# Half_Slave.net
KiCad netlist of a schematic drawn in Altium Designer
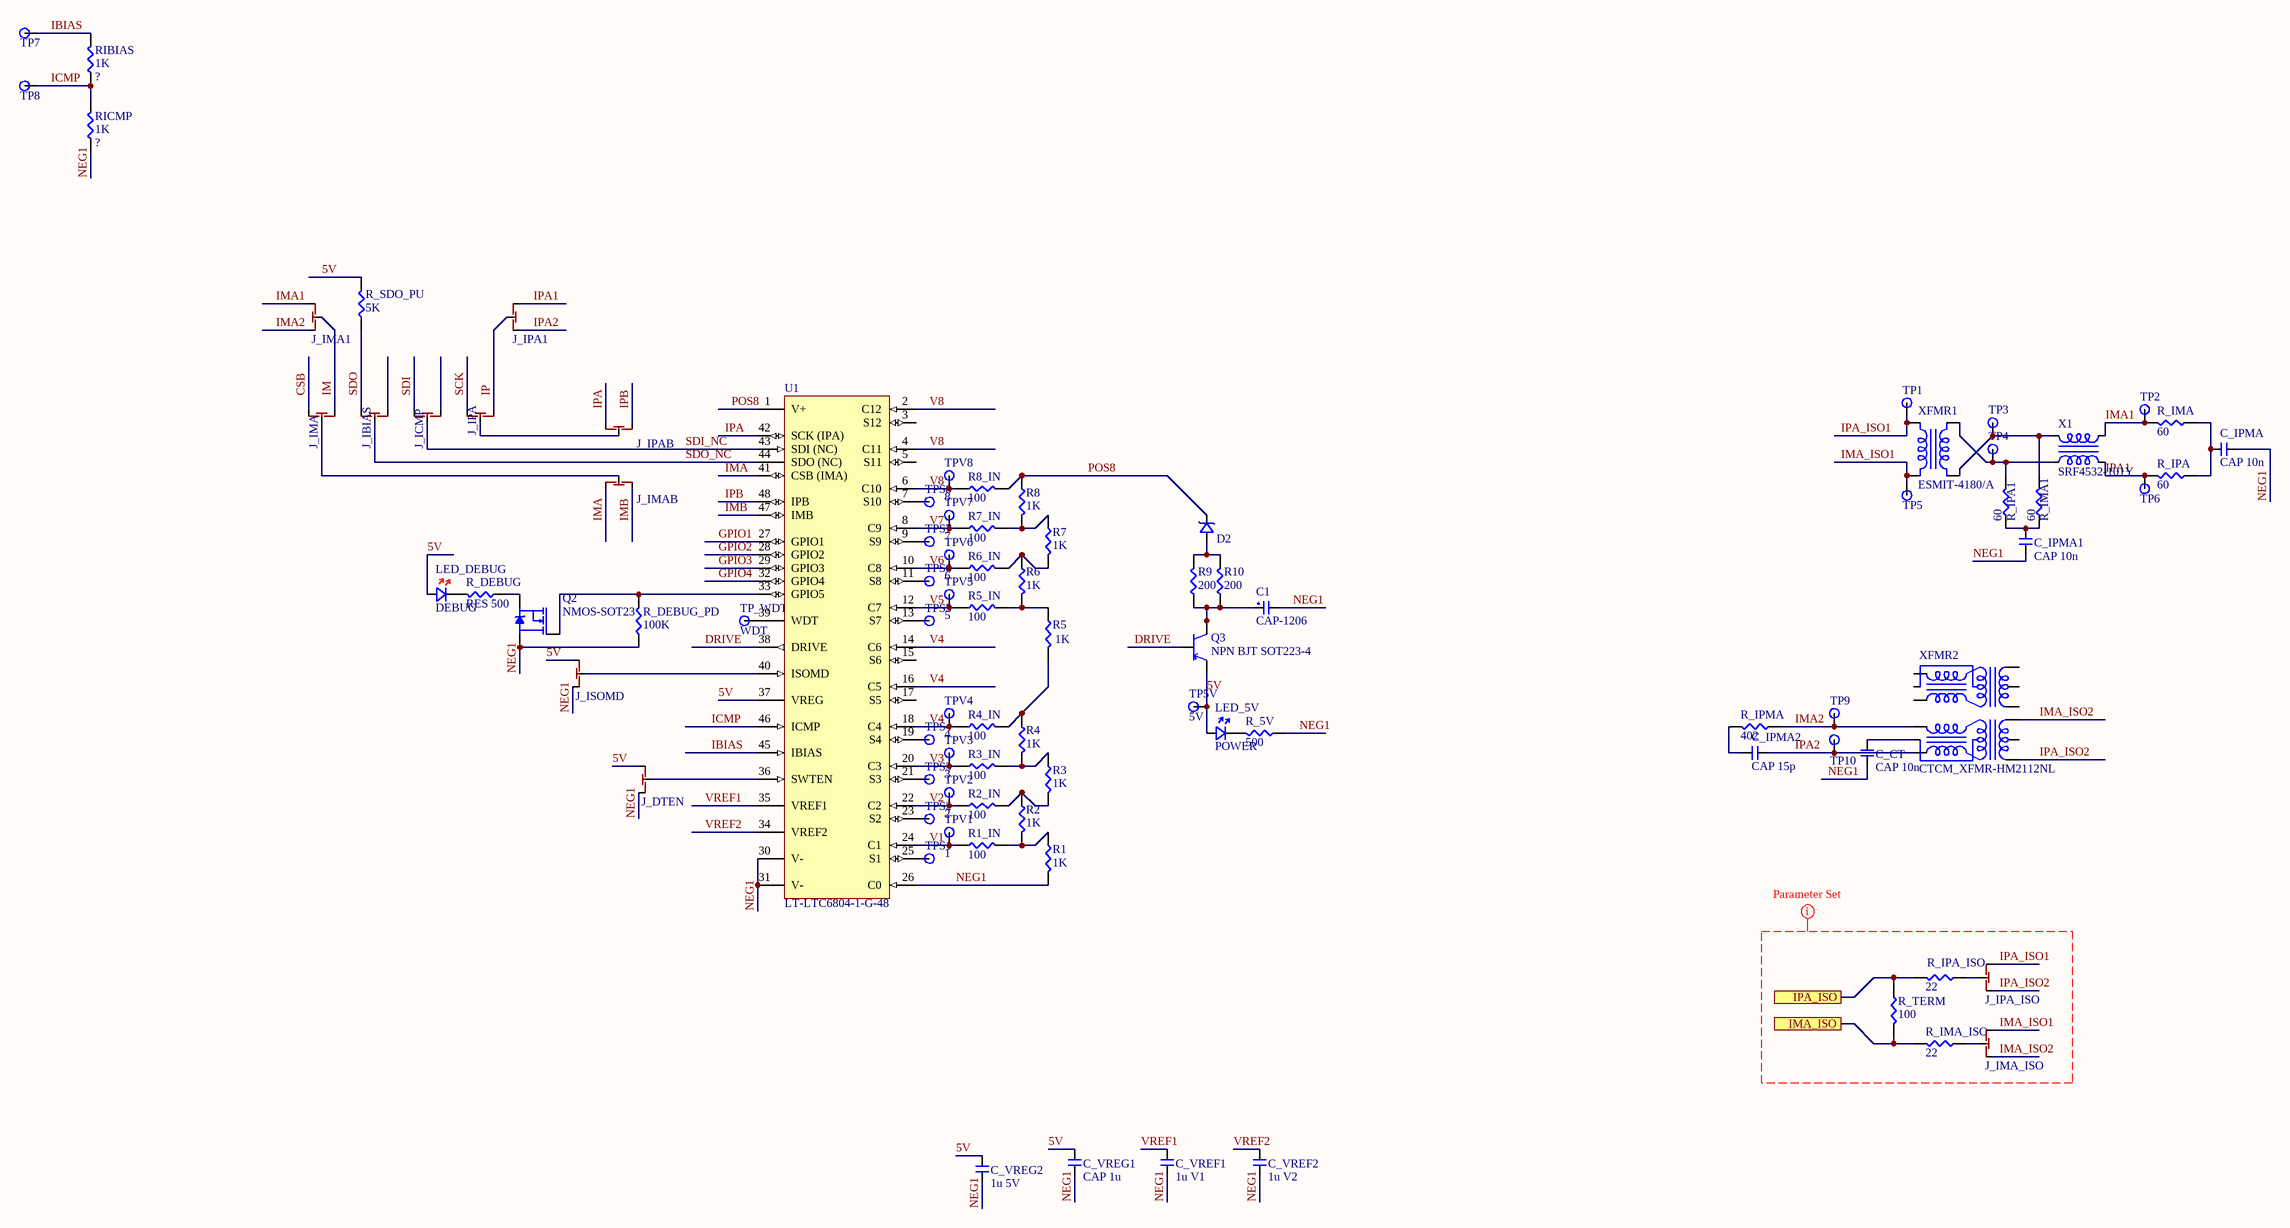
[diagram p0: Half_Slave.SchDoc]

(export (version "E")
  (design (tool "Eeschema 10.0.6"))
  (components
    (comp (ref "C1")
      (value "CAP-1206")
      (footprint "CAPCP3216X16N")
      (libsource (lib "LTC6811") (part "CAP-1206"))
    )
    (comp (ref "C_CT")
      (value "CAP 10n")
      (footprint "CAP-0603")
      (description "CAP-0603")
      (libsource (lib "ife18_TS_BMS_LTC6813_v2_Library") (part "CAP-0603"))
    )
    (comp (ref "C_IPMA")
      (value "CAP 10n")
      (footprint "CAP-0603")
      (description "CAP-0603")
      (libsource (lib "ife18_TS_BMS_LTC6813_v2_Library") (part "CAP-0603"))
    )
    (comp (ref "C_IPMA1")
      (value "CAP 10n")
      (footprint "CAP-0603")
      (description "CAP-0603")
      (libsource (lib "ife18_TS_BMS_LTC6813_v2_Library") (part "CAP-0603"))
    )
    (comp (ref "C_IPMA2")
      (value "CAP 15p")
      (footprint "CAP-0603")
      (description "CAP-0603")
      (libsource (lib "ife18_TS_BMS_LTC6813_v2_Library") (part "CAP-0603"))
    )
    (comp (ref "C_VREF1")
      (value "1u V1")
      (footprint "CAP-0603")
      (description "CAP-0603")
      (libsource (lib "altium-import") (part "root_1_CAP-0603_"))
    )
    (comp (ref "C_VREF2")
      (value "1u V2")
      (footprint "CAP-0603")
      (description "CAP-0603")
      (libsource (lib "altium-import") (part "root_1_CAP-0603_"))
    )
    (comp (ref "C_VREG1")
      (value "CAP 1u")
      (footprint "CAP-0603")
      (description "CAP-0603")
      (libsource (lib "altium-import") (part "root_1_CAP-0603_"))
    )
    (comp (ref "C_VREG2")
      (value "1u 5V")
      (footprint "CAP-0603")
      (description "CAP-0603")
      (libsource (lib "altium-import") (part "root_1_CAP-0603_"))
    )
    (comp (ref "D2") (value "?") (footprint "SMB") (libsource (lib "ife19_Elec_Library") (part "DIODE-SMB")))
    (comp (ref "J_DTEN")
      (value "DPDT Solder Jumper")
      (footprint "DPDT Solder")
      (libsource (lib "LTC6811") (part "DPDT Solder"))
    )
    (comp (ref "J_IBIAS")
      (value "DPDT Solder Jumper")
      (footprint "DPDT Solder")
      (libsource (lib "LTC6811") (part "DPDT Solder"))
    )
    (comp (ref "J_ICMP")
      (value "DPDT Solder Jumper")
      (footprint "DPDT Solder")
      (libsource (lib "LTC6811") (part "DPDT Solder"))
    )
    (comp (ref "J_IMA")
      (value "DPDT Solder Jumper")
      (footprint "DPDT Solder")
      (libsource (lib "LTC6811") (part "DPDT Solder"))
    )
    (comp (ref "J_IMA1")
      (value "DPDT Solder Jumper")
      (footprint "DPDT Solder")
      (libsource (lib "LTC6811") (part "DPDT Solder"))
    )
    (comp (ref "J_IMAB")
      (value "DPDT Solder Jumper")
      (footprint "DPDT Solder")
      (libsource (lib "LTC6811") (part "DPDT Solder"))
    )
    (comp (ref "J_IMA_ISO")
      (value "DPDT Solder Jumper")
      (footprint "DPDT Solder")
      (libsource (lib "LTC6811") (part "DPDT Solder"))
    )
    (comp (ref "J_IPA")
      (value "DPDT Solder Jumper")
      (footprint "DPDT Solder")
      (libsource (lib "LTC6811") (part "DPDT Solder"))
    )
    (comp (ref "J_IPA1")
      (value "DPDT Solder Jumper")
      (footprint "DPDT Solder")
      (libsource (lib "LTC6811") (part "DPDT Solder"))
    )
    (comp (ref "J_IPAB")
      (value "DPDT Solder Jumper")
      (footprint "DPDT Solder")
      (libsource (lib "LTC6811") (part "DPDT Solder"))
    )
    (comp (ref "J_IPA_ISO")
      (value "DPDT Solder Jumper")
      (footprint "DPDT Solder")
      (libsource (lib "LTC6811") (part "DPDT Solder"))
    )
    (comp (ref "J_ISOMD")
      (value "DPDT Solder Jumper")
      (footprint "DPDT Solder")
      (libsource (lib "LTC6811") (part "DPDT Solder"))
    )
    (comp (ref "LED_5V")
      (value "POWER")
      (footprint "LEDBLUE-0603")
      (libsource (lib "ife19_Elec_Library") (part "LEDBLUE-0603"))
    )
    (comp (ref "LED_DEBUG")
      (value "DEBUG")
      (footprint "LEDRED-0603")
      (libsource (lib "ife19_Elec_Library") (part "LEDRED-0603"))
    )
    (comp (ref "Q2")
      (value "NMOS-SOT23")
      (footprint "SOT23")
      (libsource (lib "ife19_Elec_Library") (part "NMOS-SOT23"))
    )
    (comp (ref "Q3")
      (value "NPN BJT SOT223-4")
      (footprint "SOT223")
      (description "BCP54,115")
      (libsource (lib "ife19_Elec_Library") (part "NPN_SOT223-4"))
    )
    (comp (ref "R1")
      (value "1K")
      (footprint "RES-0603")
      (libsource (lib "ife18_TS_BMS_LTC6813_v2_Library") (part "RES-0603"))
    )
    (comp (ref "R1_IN")
      (value "100")
      (footprint "RES-0603")
      (libsource (lib "ife18_TS_BMS_LTC6813_v2_Library") (part "RES-0603"))
    )
    (comp (ref "R2")
      (value "1K")
      (footprint "RES-0603")
      (libsource (lib "ife18_TS_BMS_LTC6813_v2_Library") (part "RES-0603"))
    )
    (comp (ref "R2_IN")
      (value "100")
      (footprint "RES-0603")
      (libsource (lib "ife18_TS_BMS_LTC6813_v2_Library") (part "RES-0603"))
    )
    (comp (ref "R3")
      (value "1K")
      (footprint "RES-0603")
      (libsource (lib "ife18_TS_BMS_LTC6813_v2_Library") (part "RES-0603"))
    )
    (comp (ref "R3_IN")
      (value "100")
      (footprint "RES-0603")
      (libsource (lib "ife18_TS_BMS_LTC6813_v2_Library") (part "RES-0603"))
    )
    (comp (ref "R4")
      (value "1K")
      (footprint "RES-0603")
      (libsource (lib "ife18_TS_BMS_LTC6813_v2_Library") (part "RES-0603"))
    )
    (comp (ref "R4_IN")
      (value "100")
      (footprint "RES-0603")
      (libsource (lib "ife18_TS_BMS_LTC6813_v2_Library") (part "RES-0603"))
    )
    (comp (ref "R5")
      (value "1K")
      (footprint "RES-0603")
      (libsource (lib "ife18_TS_BMS_LTC6813_v2_Library") (part "RES-0603"))
    )
    (comp (ref "R5_IN")
      (value "100")
      (footprint "RES-0603")
      (libsource (lib "ife18_TS_BMS_LTC6813_v2_Library") (part "RES-0603"))
    )
    (comp (ref "R6")
      (value "1K")
      (footprint "RES-0603")
      (libsource (lib "ife18_TS_BMS_LTC6813_v2_Library") (part "RES-0603"))
    )
    (comp (ref "R6_IN")
      (value "100")
      (footprint "RES-0603")
      (libsource (lib "ife18_TS_BMS_LTC6813_v2_Library") (part "RES-0603"))
    )
    (comp (ref "R7")
      (value "1K")
      (footprint "RES-0603")
      (libsource (lib "ife18_TS_BMS_LTC6813_v2_Library") (part "RES-0603"))
    )
    (comp (ref "R7_IN")
      (value "100")
      (footprint "RES-0603")
      (libsource (lib "ife18_TS_BMS_LTC6813_v2_Library") (part "RES-0603"))
    )
    (comp (ref "R8")
      (value "1K")
      (footprint "RES-0603")
      (libsource (lib "ife18_TS_BMS_LTC6813_v2_Library") (part "RES-0603"))
    )
    (comp (ref "R8_IN")
      (value "100")
      (footprint "RES-0603")
      (libsource (lib "ife18_TS_BMS_LTC6813_v2_Library") (part "RES-0603"))
    )
    (comp (ref "R9")
      (value "200")
      (footprint "RES-0603")
      (libsource (lib "ife18_TS_BMS_LTC6813_v2_Library") (part "RES-0603"))
    )
    (comp (ref "R10")
      (value "200")
      (footprint "RES-0603")
      (libsource (lib "ife18_TS_BMS_LTC6813_v2_Library") (part "RES-0603"))
    )
    (comp (ref "RIBIAS")
      (value "1K")
      (footprint "RES-0603")
      (description "RES SMD 0603")
      (fields (field (name "PART") "RES_0603") (field (name "ALTIUM_VALUE") "?"))
      (libsource (lib "IFE") (part "RES"))
    )
    (comp (ref "RICMP")
      (value "1K")
      (footprint "RES-0603")
      (description "RES SMD 0603")
      (fields (field (name "PART") "RES_0603") (field (name "ALTIUM_VALUE") "?"))
      (libsource (lib "IFE") (part "RES"))
    )
    (comp (ref "R_5V")
      (value "500")
      (footprint "RES-0603")
      (libsource (lib "altium-import") (part "root_2_RES-0603_"))
    )
    (comp (ref "R_DEBUG")
      (value "RES 500")
      (footprint "RES-0603")
      (libsource (lib "altium-import") (part "root_2_RES-0603_"))
    )
    (comp (ref "R_DEBUG_PD")
      (value "100K")
      (footprint "RES-0603")
      (libsource (lib "ife18_TS_BMS_LTC6813_v2_Library") (part "RES-0603"))
    )
    (comp (ref "R_IMA")
      (value "60")
      (footprint "RES-0603")
      (libsource (lib "ife18_TS_BMS_LTC6813_v2_Library") (part "RES-0603"))
    )
    (comp (ref "R_IMA1")
      (value "60")
      (footprint "RES-0603")
      (libsource (lib "ife18_TS_BMS_LTC6813_v2_Library") (part "RES-0603"))
    )
    (comp (ref "R_IMA_ISO")
      (value "22")
      (footprint "RES-0603")
      (libsource (lib "ife18_TS_BMS_LTC6813_v2_Library") (part "RES-0603"))
    )
    (comp (ref "R_IPA")
      (value "60")
      (footprint "RES-0603")
      (libsource (lib "ife18_TS_BMS_LTC6813_v2_Library") (part "RES-0603"))
    )
    (comp (ref "R_IPA1")
      (value "60")
      (footprint "RES-0603")
      (libsource (lib "ife18_TS_BMS_LTC6813_v2_Library") (part "RES-0603"))
    )
    (comp (ref "R_IPA_ISO")
      (value "22")
      (footprint "RES-0603")
      (libsource (lib "ife18_TS_BMS_LTC6813_v2_Library") (part "RES-0603"))
    )
    (comp (ref "R_IPMA")
      (value "402")
      (footprint "RES-0603")
      (libsource (lib "ife18_TS_BMS_LTC6813_v2_Library") (part "RES-0603"))
    )
    (comp (ref "R_SDO_PU")
      (value "5K")
      (footprint "RES-0603")
      (libsource (lib "ife18_TS_BMS_LTC6813_v2_Library") (part "RES-0603"))
    )
    (comp (ref "R_TERM")
      (value "100")
      (footprint "RES-0603")
      (libsource (lib "ife18_TS_BMS_LTC6813_v2_Library") (part "RES-0603"))
    )
    (comp (ref "TP1")
      (value "IP_ISO")
      (footprint "Testpoint")
      (libsource (lib "ife19_Elec_Library") (part "Testpoint"))
    )
    (comp (ref "TP2")
      (value "IMA")
      (footprint "Testpoint")
      (libsource (lib "ife19_Elec_Library") (part "Testpoint"))
    )
    (comp (ref "TP3")
      (value "IM_F")
      (footprint "Testpoint")
      (libsource (lib "ife19_Elec_Library") (part "Testpoint"))
    )
    (comp (ref "TP4")
      (value "IP_F")
      (footprint "Testpoint")
      (libsource (lib "ife19_Elec_Library") (part "Testpoint"))
    )
    (comp (ref "TP5")
      (value "IM_ISO")
      (footprint "Testpoint")
      (libsource (lib "ife19_Elec_Library") (part "Testpoint"))
    )
    (comp (ref "TP5V")
      (value "5V")
      (footprint "Testpoint")
      (libsource (lib "ife19_Elec_Library") (part "Testpoint"))
    )
    (comp (ref "TP6")
      (value "IPA")
      (footprint "Testpoint")
      (libsource (lib "ife19_Elec_Library") (part "Testpoint"))
    )
    (comp (ref "TP7")
      (value "IBIAS")
      (footprint "Testpoint")
      (libsource (lib "ife19_Elec_Library") (part "Testpoint"))
    )
    (comp (ref "TP8")
      (value "ICMP")
      (footprint "Testpoint")
      (libsource (lib "ife19_Elec_Library") (part "Testpoint"))
    )
    (comp (ref "TP9")
      (value "IMA")
      (footprint "Testpoint")
      (libsource (lib "ife19_Elec_Library") (part "Testpoint"))
    )
    (comp (ref "TP10")
      (value "IPA")
      (footprint "Testpoint")
      (libsource (lib "ife19_Elec_Library") (part "Testpoint"))
    )
    (comp (ref "TPS1")
      (value "~")
      (footprint "Testpoint")
      (libsource (lib "ife19_Elec_Library") (part "Testpoint"))
    )
    (comp (ref "TPS2")
      (value "~")
      (footprint "Testpoint")
      (libsource (lib "ife19_Elec_Library") (part "Testpoint"))
    )
    (comp (ref "TPS3")
      (value "~")
      (footprint "Testpoint")
      (libsource (lib "ife19_Elec_Library") (part "Testpoint"))
    )
    (comp (ref "TPS4")
      (value "~")
      (footprint "Testpoint")
      (libsource (lib "ife19_Elec_Library") (part "Testpoint"))
    )
    (comp (ref "TPS5")
      (value "~")
      (footprint "Testpoint")
      (libsource (lib "ife19_Elec_Library") (part "Testpoint"))
    )
    (comp (ref "TPS6")
      (value "~")
      (footprint "Testpoint")
      (libsource (lib "ife19_Elec_Library") (part "Testpoint"))
    )
    (comp (ref "TPS7")
      (value "~")
      (footprint "Testpoint")
      (libsource (lib "ife19_Elec_Library") (part "Testpoint"))
    )
    (comp (ref "TPS8")
      (value "~")
      (footprint "Testpoint")
      (libsource (lib "ife19_Elec_Library") (part "Testpoint"))
    )
    (comp (ref "TPV1")
      (value "1")
      (footprint "Testpoint")
      (libsource (lib "ife19_Elec_Library") (part "Testpoint"))
    )
    (comp (ref "TPV2")
      (value "2")
      (footprint "Testpoint")
      (libsource (lib "ife19_Elec_Library") (part "Testpoint"))
    )
    (comp (ref "TPV3")
      (value "3")
      (footprint "Testpoint")
      (libsource (lib "ife19_Elec_Library") (part "Testpoint"))
    )
    (comp (ref "TPV4")
      (value "4")
      (footprint "Testpoint")
      (libsource (lib "ife19_Elec_Library") (part "Testpoint"))
    )
    (comp (ref "TPV5")
      (value "5")
      (footprint "Testpoint")
      (libsource (lib "ife19_Elec_Library") (part "Testpoint"))
    )
    (comp (ref "TPV6")
      (value "6")
      (footprint "Testpoint")
      (libsource (lib "ife19_Elec_Library") (part "Testpoint"))
    )
    (comp (ref "TPV7")
      (value "7")
      (footprint "Testpoint")
      (libsource (lib "ife19_Elec_Library") (part "Testpoint"))
    )
    (comp (ref "TPV8")
      (value "8")
      (footprint "Testpoint")
      (libsource (lib "ife19_Elec_Library") (part "Testpoint"))
    )
    (comp (ref "TP_WDT")
      (value "WDT")
      (footprint "Testpoint")
      (libsource (lib "ife19_Elec_Library") (part "Testpoint"))
    )
    (comp (ref "U1")
      (value "LT-LTC6804-1-G-48")
      (footprint "SSOP-48N")
      (libsource (lib "LTC6811") (part "LT-LTC6804-1-G-48"))
    )
    (comp (ref "X1")
      (value "SRF4532-101Y")
      (footprint "SRF4532")
      (libsource (lib "ife19_Elec_Library") (part "CMC_SRF4532"))
    )
    (comp (ref "XFMR1")
      (value "ESMIT-4180/A")
      (footprint "ISOXFMR_ESMIT4180")
      (libsource (lib "ife19_Elec_Library") (part "ISOXFMR_ESMIT4180"))
    )
    (comp (ref "XFMR2")
      (value "CTCM_XFMR-HM2112NL")
      (footprint "HM2112NL")
      (libsource (lib "ife19_Elec_Library") (part "CTCM_XFMR-HM2112NL"))
    )
  )
  (nets
    (net (code "1") (name "/5V") (class "Default")
      (node (ref "C_VREG1") (pin "2") (pinfunction "2_2") (pintype "passive"))
      (node (ref "C_VREG2") (pin "2") (pinfunction "2_2") (pintype "passive"))
      (node (ref "J_DTEN") (pin "2") (pintype "passive"))
      (node (ref "J_ISOMD") (pin "2") (pintype "passive"))
      (node (ref "LED_5V") (pin "A") (pinfunction "A_A") (pintype "passive"))
      (node (ref "LED_DEBUG") (pin "A") (pinfunction "A_A") (pintype "passive"))
      (node (ref "Q3") (pin "3") (pinfunction "E_3") (pintype "passive"))
      (node (ref "R_SDO_PU") (pin "2") (pinfunction "2_2") (pintype "passive"))
      (node (ref "TP5V") (pin "1") (pinfunction "1_1") (pintype "passive"))
      (node (ref "U1") (pin "37") (pinfunction "VREG_37") (pintype "power_in"))
    )
    (net (code "2") (name "/CSB") (class "Default") (node (ref "J_IMA") (pin "1") (pintype "passive")))
    (net (code "3") (name "/DRIVE") (class "Default")
      (node (ref "Q3") (pin "1") (pinfunction "B_1") (pintype "passive"))
      (node (ref "U1") (pin "38") (pinfunction "DRIVE_38") (pintype "output"))
    )
    (net (code "4") (name "/GPIO1") (class "Default")
      (node (ref "U1") (pin "27") (pinfunction "GPIO1_27") (pintype "bidirectional"))
    )
    (net (code "5") (name "/GPIO2") (class "Default")
      (node (ref "U1") (pin "28") (pinfunction "GPIO2_28") (pintype "bidirectional"))
    )
    (net (code "6") (name "/GPIO3") (class "Default")
      (node (ref "U1") (pin "29") (pinfunction "GPIO3_29") (pintype "bidirectional"))
    )
    (net (code "7") (name "/GPIO4") (class "Default")
      (node (ref "U1") (pin "32") (pinfunction "GPIO4_32") (pintype "bidirectional"))
    )
    (net (code "8") (name "/IBIAS") (class "Default")
      (node (ref "RIBIAS") (pin "2") (pinfunction "2_2") (pintype "passive"))
      (node (ref "TP7") (pin "1") (pinfunction "1_1") (pintype "passive"))
      (node (ref "U1") (pin "45") (pinfunction "IBIAS_45") (pintype "input"))
    )
    (net (code "9") (name "/ICMP") (class "Default")
      (node (ref "RIBIAS") (pin "1") (pinfunction "1_1") (pintype "passive"))
      (node (ref "RICMP") (pin "2") (pinfunction "2_2") (pintype "passive"))
      (node (ref "TP8") (pin "1") (pinfunction "1_1") (pintype "passive"))
      (node (ref "U1") (pin "46") (pinfunction "ICMP_46") (pintype "input"))
    )
    (net (code "10") (name "/IM") (class "Default")
      (node (ref "J_IMA") (pin "2") (pintype "passive"))
      (node (ref "J_IMA1") (pin "3") (pintype "passive"))
    )
    (net (code "11") (name "/IMA") (class "Default")
      (node (ref "J_IMAB") (pin "2") (pintype "passive"))
      (node (ref "U1") (pin "41") (pinfunction "CSB_(IMA)_41") (pintype "bidirectional"))
    )
    (net (code "12") (name "/IMA1") (class "Default")
      (node (ref "J_IMA1") (pin "2") (pintype "passive"))
      (node (ref "R_IMA") (pin "2") (pinfunction "2_2") (pintype "passive"))
      (node (ref "TP2") (pin "1") (pinfunction "1_1") (pintype "passive"))
      (node (ref "X1") (pin "1") (pinfunction "1_1") (pintype "passive"))
    )
    (net (code "13") (name "/IMA2") (class "Default")
      (node (ref "J_IMA1") (pin "1") (pintype "passive"))
      (node (ref "R_IPMA") (pin "1") (pinfunction "1_1") (pintype "passive"))
      (node (ref "TP9") (pin "1") (pinfunction "1_1") (pintype "passive"))
      (node (ref "XFMR2") (pin "9") (pinfunction "9_9") (pintype "passive"))
    )
    (net (code "14") (name "/IMA_ISO") (class "Default")
      (node (ref "R_IMA_ISO") (pin "2") (pinfunction "2_2") (pintype "passive"))
      (node (ref "R_TERM") (pin "2") (pinfunction "2_2") (pintype "passive"))
    )
    (net (code "15") (name "/IMA_ISO1") (class "Default")
      (node (ref "J_IMA_ISO") (pin "2") (pintype "passive"))
      (node (ref "TP5") (pin "1") (pinfunction "1_1") (pintype "passive"))
      (node (ref "XFMR1") (pin "1") (pinfunction "1_1") (pintype "passive"))
    )
    (net (code "16") (name "/IMA_ISO2") (class "Default")
      (node (ref "J_IMA_ISO") (pin "1") (pintype "passive"))
      (node (ref "XFMR2") (pin "4") (pinfunction "4_4") (pintype "passive"))
    )
    (net (code "17") (name "/IMB") (class "Default")
      (node (ref "J_IMAB") (pin "1") (pintype "passive"))
      (node (ref "U1") (pin "47") (pinfunction "IMB_47") (pintype "bidirectional"))
    )
    (net (code "18") (name "/IP") (class "Default")
      (node (ref "J_IPA") (pin "2") (pintype "passive"))
      (node (ref "J_IPA1") (pin "3") (pintype "passive"))
    )
    (net (code "19") (name "/IPA") (class "Default")
      (node (ref "J_IPAB") (pin "2") (pintype "passive"))
      (node (ref "U1") (pin "42") (pinfunction "SCK_(IPA)_42") (pintype "bidirectional"))
    )
    (net (code "20") (name "/IPA1") (class "Default")
      (node (ref "J_IPA1") (pin "2") (pintype "passive"))
      (node (ref "R_IPA") (pin "2") (pinfunction "2_2") (pintype "passive"))
      (node (ref "TP6") (pin "1") (pinfunction "1_1") (pintype "passive"))
      (node (ref "X1") (pin "4") (pinfunction "4_4") (pintype "passive"))
    )
    (net (code "21") (name "/IPA2") (class "Default")
      (node (ref "C_IPMA2") (pin "1") (pinfunction "1_1") (pintype "passive"))
      (node (ref "J_IPA1") (pin "1") (pintype "passive"))
      (node (ref "TP10") (pin "1") (pinfunction "1_1") (pintype "passive"))
      (node (ref "XFMR2") (pin "7") (pinfunction "7_7") (pintype "passive"))
    )
    (net (code "22") (name "/IPA_ISO") (class "Default")
      (node (ref "R_IPA_ISO") (pin "2") (pinfunction "2_2") (pintype "passive"))
      (node (ref "R_TERM") (pin "1") (pinfunction "1_1") (pintype "passive"))
    )
    (net (code "23") (name "/IPA_ISO1") (class "Default")
      (node (ref "J_IPA_ISO") (pin "2") (pintype "passive"))
      (node (ref "TP1") (pin "1") (pinfunction "1_1") (pintype "passive"))
      (node (ref "XFMR1") (pin "2") (pinfunction "2_2") (pintype "passive"))
    )
    (net (code "24") (name "/IPA_ISO2") (class "Default")
      (node (ref "J_IPA_ISO") (pin "1") (pintype "passive"))
      (node (ref "XFMR2") (pin "6") (pinfunction "6_6") (pintype "passive"))
    )
    (net (code "25") (name "/IPB") (class "Default")
      (node (ref "J_IPAB") (pin "1") (pintype "passive"))
      (node (ref "U1") (pin "48") (pinfunction "IPB_48") (pintype "bidirectional"))
    )
    (net (code "26") (name "/NEG1") (class "Default")
      (node (ref "C1") (pin "2") (pinfunction "2_2") (pintype "passive"))
      (node (ref "C_CT") (pin "2") (pinfunction "2_2") (pintype "passive"))
      (node (ref "C_IPMA") (pin "1") (pinfunction "1_1") (pintype "passive"))
      (node (ref "C_IPMA1") (pin "1") (pinfunction "1_1") (pintype "passive"))
      (node (ref "C_VREF1") (pin "1") (pinfunction "1_1") (pintype "passive"))
      (node (ref "C_VREF2") (pin "1") (pinfunction "1_1") (pintype "passive"))
      (node (ref "C_VREG1") (pin "1") (pinfunction "1_1") (pintype "passive"))
      (node (ref "C_VREG2") (pin "1") (pinfunction "1_1") (pintype "passive"))
      (node (ref "J_DTEN") (pin "1") (pintype "passive"))
      (node (ref "J_ISOMD") (pin "1") (pintype "passive"))
      (node (ref "Q2") (pin "2") (pinfunction "S_2") (pintype "passive"))
      (node (ref "R1") (pin "2") (pinfunction "2_2") (pintype "passive"))
      (node (ref "RICMP") (pin "1") (pinfunction "1_1") (pintype "passive"))
      (node (ref "R_5V") (pin "1") (pinfunction "1_1") (pintype "passive"))
      (node (ref "R_DEBUG_PD") (pin "1") (pinfunction "1_1") (pintype "passive"))
      (node (ref "U1") (pin "26") (pinfunction "C0_26") (pintype "input"))
      (node (ref "U1") (pin "30") (pinfunction "V-_30") (pintype "power_in"))
      (node (ref "U1") (pin "31") (pinfunction "V-_31") (pintype "power_in"))
    )
    (net (code "27") (name "/POS8") (class "Default")
      (node (ref "D2") (pin "K") (pinfunction "K_K") (pintype "passive"))
      (node (ref "R8") (pin "1") (pinfunction "1_1") (pintype "passive"))
      (node (ref "R8_IN") (pin "2") (pinfunction "2_2") (pintype "passive"))
      (node (ref "U1") (pin "1") (pinfunction "V+_1") (pintype "power_in"))
    )
    (net (code "28") (name "/SCK") (class "Default") (node (ref "J_IPA") (pin "1") (pintype "passive")))
    (net (code "29") (name "/SDI") (class "Default") (node (ref "J_ICMP") (pin "1") (pintype "passive")))
    (net (code "30") (name "/SDI_NC") (class "Default")
      (node (ref "J_ICMP") (pin "3") (pintype "passive"))
      (node (ref "U1") (pin "43") (pinfunction "SDI_(NC)_43") (pintype "input"))
    )
    (net (code "31") (name "/SDO") (class "Default")
      (node (ref "J_IBIAS") (pin "1") (pintype "passive"))
      (node (ref "R_SDO_PU") (pin "1") (pinfunction "1_1") (pintype "passive"))
    )
    (net (code "32") (name "/SDO_NC") (class "Default")
      (node (ref "J_IBIAS") (pin "3") (pintype "passive"))
      (node (ref "U1") (pin "44") (pinfunction "SDO_(NC)_44") (pintype "open_collector"))
    )
    (net (code "33") (name "/V1") (class "Default")
      (node (ref "R1_IN") (pin "1") (pinfunction "1_1") (pintype "passive"))
      (node (ref "TPV1") (pin "1") (pinfunction "1_1") (pintype "passive"))
      (node (ref "U1") (pin "24") (pinfunction "C1_24") (pintype "input"))
    )
    (net (code "34") (name "/V2") (class "Default")
      (node (ref "R2_IN") (pin "1") (pinfunction "1_1") (pintype "passive"))
      (node (ref "TPV2") (pin "1") (pinfunction "1_1") (pintype "passive"))
      (node (ref "U1") (pin "22") (pinfunction "C2_22") (pintype "input"))
    )
    (net (code "35") (name "/V3") (class "Default")
      (node (ref "R3_IN") (pin "1") (pinfunction "1_1") (pintype "passive"))
      (node (ref "TPV3") (pin "1") (pinfunction "1_1") (pintype "passive"))
      (node (ref "U1") (pin "20") (pinfunction "C3_20") (pintype "input"))
    )
    (net (code "36") (name "/V4") (class "Default")
      (node (ref "R4_IN") (pin "1") (pinfunction "1_1") (pintype "passive"))
      (node (ref "TPV4") (pin "1") (pinfunction "1_1") (pintype "passive"))
      (node (ref "U1") (pin "14") (pinfunction "C6_14") (pintype "input"))
      (node (ref "U1") (pin "16") (pinfunction "C5_16") (pintype "input"))
      (node (ref "U1") (pin "18") (pinfunction "C4_18") (pintype "input"))
    )
    (net (code "37") (name "/V5") (class "Default")
      (node (ref "R5_IN") (pin "1") (pinfunction "1_1") (pintype "passive"))
      (node (ref "TPV5") (pin "1") (pinfunction "1_1") (pintype "passive"))
      (node (ref "U1") (pin "12") (pinfunction "C7_12") (pintype "input"))
    )
    (net (code "38") (name "/V6") (class "Default")
      (node (ref "R6_IN") (pin "1") (pinfunction "1_1") (pintype "passive"))
      (node (ref "TPV6") (pin "1") (pinfunction "1_1") (pintype "passive"))
      (node (ref "U1") (pin "10") (pinfunction "C8_10") (pintype "input"))
    )
    (net (code "39") (name "/V7") (class "Default")
      (node (ref "R7_IN") (pin "1") (pinfunction "1_1") (pintype "passive"))
      (node (ref "TPV7") (pin "1") (pinfunction "1_1") (pintype "passive"))
      (node (ref "U1") (pin "8") (pinfunction "C9_8") (pintype "input"))
    )
    (net (code "40") (name "/V8") (class "Default")
      (node (ref "R8_IN") (pin "1") (pinfunction "1_1") (pintype "passive"))
      (node (ref "TPV8") (pin "1") (pinfunction "1_1") (pintype "passive"))
      (node (ref "U1") (pin "2") (pinfunction "C12_2") (pintype "input"))
      (node (ref "U1") (pin "4") (pinfunction "C11_4") (pintype "input"))
      (node (ref "U1") (pin "6") (pinfunction "C10_6") (pintype "input"))
    )
    (net (code "41") (name "/VREF1") (class "Default")
      (node (ref "C_VREF1") (pin "2") (pinfunction "2_2") (pintype "passive"))
      (node (ref "U1") (pin "35") (pinfunction "VREF1_35") (pintype "passive"))
    )
    (net (code "42") (name "/VREF2") (class "Default")
      (node (ref "C_VREF2") (pin "2") (pinfunction "2_2") (pintype "passive"))
      (node (ref "U1") (pin "34") (pinfunction "VREF2_34") (pintype "passive"))
    )
    (net (code "43") (name "Net-(C1-Pad1)") (class "Default")
      (node (ref "C1") (pin "1") (pinfunction "1_1") (pintype "passive"))
      (node (ref "Q3") (pin "2") (pinfunction "C_2") (pintype "passive"))
      (node (ref "Q3") (pin "4") (pinfunction "C_4") (pintype "passive"))
      (node (ref "R10") (pin "1") (pinfunction "1_1") (pintype "passive"))
      (node (ref "R9") (pin "1") (pinfunction "1_1") (pintype "passive"))
    )
    (net (code "44") (name "Net-(C_CT-Pad1)") (class "Default")
      (node (ref "C_CT") (pin "1") (pinfunction "1_1") (pintype "passive"))
      (node (ref "XFMR2") (pin "8") (pinfunction "8_8") (pintype "passive"))
    )
    (net (code "45") (name "Net-(C_IPMA-Pad2)") (class "Default")
      (node (ref "C_IPMA") (pin "2") (pinfunction "2_2") (pintype "passive"))
      (node (ref "R_IMA") (pin "1") (pinfunction "1_1") (pintype "passive"))
      (node (ref "R_IPA") (pin "1") (pinfunction "1_1") (pintype "passive"))
    )
    (net (code "46") (name "Net-(C_IPMA1-Pad2)") (class "Default")
      (node (ref "C_IPMA1") (pin "2") (pinfunction "2_2") (pintype "passive"))
      (node (ref "R_IMA1") (pin "1") (pinfunction "1_1") (pintype "passive"))
      (node (ref "R_IPA1") (pin "1") (pinfunction "1_1") (pintype "passive"))
    )
    (net (code "47") (name "Net-(C_IPMA2-Pad2)") (class "Default")
      (node (ref "C_IPMA2") (pin "2") (pinfunction "2_2") (pintype "passive"))
      (node (ref "R_IPMA") (pin "2") (pinfunction "2_2") (pintype "passive"))
    )
    (net (code "48") (name "Net-(D2-PadA)") (class "Default")
      (node (ref "D2") (pin "A") (pinfunction "A_A") (pintype "passive"))
      (node (ref "R10") (pin "2") (pinfunction "2_2") (pintype "passive"))
      (node (ref "R9") (pin "2") (pinfunction "2_2") (pintype "passive"))
    )
    (net (code "49") (name "Net-(J_IMA-Pad3)") (class "Default")
      (node (ref "J_IMA") (pin "3") (pintype "passive"))
      (node (ref "J_IMAB") (pin "3") (pintype "passive"))
    )
    (net (code "50") (name "Net-(J_IMA_ISO-Pad3)") (class "Default")
      (node (ref "J_IMA_ISO") (pin "3") (pintype "passive"))
      (node (ref "R_IMA_ISO") (pin "1") (pinfunction "1_1") (pintype "passive"))
    )
    (net (code "51") (name "Net-(J_IPA-Pad3)") (class "Default")
      (node (ref "J_IPA") (pin "3") (pintype "passive"))
      (node (ref "J_IPAB") (pin "3") (pintype "passive"))
    )
    (net (code "52") (name "Net-(J_IPA_ISO-Pad3)") (class "Default")
      (node (ref "J_IPA_ISO") (pin "3") (pintype "passive"))
      (node (ref "R_IPA_ISO") (pin "1") (pinfunction "1_1") (pintype "passive"))
    )
    (net (code "53") (name "Net-(LED_5V-PadK)") (class "Default")
      (node (ref "LED_5V") (pin "K") (pinfunction "K_K") (pintype "passive"))
      (node (ref "R_5V") (pin "2") (pinfunction "2_2") (pintype "passive"))
    )
    (net (code "54") (name "Net-(LED_DEBUG-PadK)") (class "Default")
      (node (ref "LED_DEBUG") (pin "K") (pinfunction "K_K") (pintype "passive"))
      (node (ref "R_DEBUG") (pin "2") (pinfunction "2_2") (pintype "passive"))
    )
    (net (code "55") (name "Net-(Q2-D)") (class "Default")
      (node (ref "Q2") (pin "3") (pinfunction "D_3") (pintype "passive"))
      (node (ref "R_DEBUG") (pin "1") (pinfunction "1_1") (pintype "passive"))
    )
    (net (code "56") (name "Net-(Q2-G)") (class "Default")
      (node (ref "Q2") (pin "1") (pinfunction "G_1") (pintype "passive"))
      (node (ref "R_DEBUG_PD") (pin "2") (pinfunction "2_2") (pintype "passive"))
      (node (ref "U1") (pin "33") (pinfunction "GPIO5_33") (pintype "bidirectional"))
    )
    (net (code "57") (name "Net-(R1-Pad1)") (class "Default")
      (node (ref "R1") (pin "1") (pinfunction "1_1") (pintype "passive"))
      (node (ref "R1_IN") (pin "2") (pinfunction "2_2") (pintype "passive"))
      (node (ref "R2") (pin "2") (pinfunction "2_2") (pintype "passive"))
    )
    (net (code "58") (name "Net-(R2-Pad1)") (class "Default")
      (node (ref "R2") (pin "1") (pinfunction "1_1") (pintype "passive"))
      (node (ref "R2_IN") (pin "2") (pinfunction "2_2") (pintype "passive"))
      (node (ref "R3") (pin "2") (pinfunction "2_2") (pintype "passive"))
    )
    (net (code "59") (name "Net-(R3-Pad1)") (class "Default")
      (node (ref "R3") (pin "1") (pinfunction "1_1") (pintype "passive"))
      (node (ref "R3_IN") (pin "2") (pinfunction "2_2") (pintype "passive"))
      (node (ref "R4") (pin "2") (pinfunction "2_2") (pintype "passive"))
    )
    (net (code "60") (name "Net-(R4-Pad1)") (class "Default")
      (node (ref "R4") (pin "1") (pinfunction "1_1") (pintype "passive"))
      (node (ref "R4_IN") (pin "2") (pinfunction "2_2") (pintype "passive"))
      (node (ref "R5") (pin "2") (pinfunction "2_2") (pintype "passive"))
    )
    (net (code "61") (name "Net-(R5-Pad1)") (class "Default")
      (node (ref "R5") (pin "1") (pinfunction "1_1") (pintype "passive"))
      (node (ref "R5_IN") (pin "2") (pinfunction "2_2") (pintype "passive"))
      (node (ref "R6") (pin "2") (pinfunction "2_2") (pintype "passive"))
    )
    (net (code "62") (name "Net-(R6-Pad1)") (class "Default")
      (node (ref "R6") (pin "1") (pinfunction "1_1") (pintype "passive"))
      (node (ref "R6_IN") (pin "2") (pinfunction "2_2") (pintype "passive"))
      (node (ref "R7") (pin "2") (pinfunction "2_2") (pintype "passive"))
    )
    (net (code "63") (name "Net-(R7-Pad1)") (class "Default")
      (node (ref "R7") (pin "1") (pinfunction "1_1") (pintype "passive"))
      (node (ref "R7_IN") (pin "2") (pinfunction "2_2") (pintype "passive"))
      (node (ref "R8") (pin "2") (pinfunction "2_2") (pintype "passive"))
    )
    (net (code "64") (name "Net-(R_IMA1-Pad2)") (class "Default")
      (node (ref "R_IMA1") (pin "2") (pinfunction "2_2") (pintype "passive"))
      (node (ref "TP3") (pin "1") (pinfunction "1_1") (pintype "passive"))
      (node (ref "X1") (pin "2") (pinfunction "2_2") (pintype "passive"))
      (node (ref "XFMR1") (pin "4") (pinfunction "4_4") (pintype "passive"))
    )
    (net (code "65") (name "Net-(R_IPA1-Pad2)") (class "Default")
      (node (ref "R_IPA1") (pin "2") (pinfunction "2_2") (pintype "passive"))
      (node (ref "TP4") (pin "1") (pinfunction "1_1") (pintype "passive"))
      (node (ref "X1") (pin "3") (pinfunction "3_3") (pintype "passive"))
      (node (ref "XFMR1") (pin "3") (pinfunction "3_3") (pintype "passive"))
    )
    (net (code "66") (name "Net-(U1-ISOMD)") (class "Default")
      (node (ref "J_ISOMD") (pin "3") (pintype "passive"))
      (node (ref "U1") (pin "40") (pinfunction "ISOMD_40") (pintype "input"))
    )
    (net (code "67") (name "Net-(U1-S1)") (class "Default")
      (node (ref "TPS1") (pin "1") (pinfunction "1_1") (pintype "passive"))
      (node (ref "U1") (pin "25") (pinfunction "S1_25") (pintype "bidirectional"))
    )
    (net (code "68") (name "Net-(U1-S2)") (class "Default")
      (node (ref "TPS2") (pin "1") (pinfunction "1_1") (pintype "passive"))
      (node (ref "U1") (pin "23") (pinfunction "S2_23") (pintype "bidirectional"))
    )
    (net (code "69") (name "Net-(U1-S3)") (class "Default")
      (node (ref "TPS3") (pin "1") (pinfunction "1_1") (pintype "passive"))
      (node (ref "U1") (pin "21") (pinfunction "S3_21") (pintype "bidirectional"))
    )
    (net (code "70") (name "Net-(U1-S4)") (class "Default")
      (node (ref "TPS4") (pin "1") (pinfunction "1_1") (pintype "passive"))
      (node (ref "U1") (pin "19") (pinfunction "S4_19") (pintype "bidirectional"))
    )
    (net (code "71") (name "Net-(U1-S7)") (class "Default")
      (node (ref "TPS5") (pin "1") (pinfunction "1_1") (pintype "passive"))
      (node (ref "U1") (pin "13") (pinfunction "S7_13") (pintype "bidirectional"))
    )
    (net (code "72") (name "Net-(U1-S8)") (class "Default")
      (node (ref "TPS6") (pin "1") (pinfunction "1_1") (pintype "passive"))
      (node (ref "U1") (pin "11") (pinfunction "S8_11") (pintype "bidirectional"))
    )
    (net (code "73") (name "Net-(U1-S9)") (class "Default")
      (node (ref "TPS7") (pin "1") (pinfunction "1_1") (pintype "passive"))
      (node (ref "U1") (pin "9") (pinfunction "S9_9") (pintype "bidirectional"))
    )
    (net (code "74") (name "Net-(U1-S10)") (class "Default")
      (node (ref "TPS8") (pin "1") (pinfunction "1_1") (pintype "passive"))
      (node (ref "U1") (pin "7") (pinfunction "S10_7") (pintype "bidirectional"))
    )
    (net (code "75") (name "Net-(U1-SWTEN)") (class "Default")
      (node (ref "J_DTEN") (pin "3") (pintype "passive"))
      (node (ref "U1") (pin "36") (pinfunction "SWTEN_36") (pintype "input"))
    )
    (net (code "76") (name "Net-(U1-WDT)") (class "Default")
      (node (ref "TP_WDT") (pin "1") (pinfunction "1_1") (pintype "passive"))
      (node (ref "U1") (pin "39") (pinfunction "WDT_39") (pintype "tri_state"))
    )
    (net (code "77") (name "unconnected-(J_IBIAS-Pad2)") (class "Default")
      (node (ref "J_IBIAS") (pin "2") (pintype "passive"))
    )
    (net (code "78") (name "unconnected-(J_ICMP-Pad2)") (class "Default")
      (node (ref "J_ICMP") (pin "2") (pintype "passive"))
    )
    (net (code "79") (name "unconnected-(U1-S5-Pad17)") (class "Default")
      (node (ref "U1") (pin "17") (pinfunction "S5_17") (pintype "bidirectional"))
    )
    (net (code "80") (name "unconnected-(U1-S6-Pad15)") (class "Default")
      (node (ref "U1") (pin "15") (pinfunction "S6_15") (pintype "bidirectional"))
    )
    (net (code "81") (name "unconnected-(U1-S11-Pad5)") (class "Default")
      (node (ref "U1") (pin "5") (pinfunction "S11_5") (pintype "bidirectional"))
    )
    (net (code "82") (name "unconnected-(U1-S12-Pad3)") (class "Default")
      (node (ref "U1") (pin "3") (pinfunction "S12_3") (pintype "bidirectional"))
    )
    (net (code "83") (name "unconnected-(XFMR2-Pad1)") (class "Default")
      (node (ref "XFMR2") (pin "1") (pinfunction "1_1") (pintype "passive"))
    )
    (net (code "84") (name "unconnected-(XFMR2-Pad2)") (class "Default")
      (node (ref "XFMR2") (pin "2") (pinfunction "2_2") (pintype "passive"))
    )
    (net (code "85") (name "unconnected-(XFMR2-Pad3)") (class "Default")
      (node (ref "XFMR2") (pin "3") (pinfunction "3_3") (pintype "passive"))
    )
    (net (code "86") (name "unconnected-(XFMR2-Pad5)") (class "Default")
      (node (ref "XFMR2") (pin "5") (pinfunction "5_5") (pintype "passive"))
    )
    (net (code "87") (name "unconnected-(XFMR2-Pad10)") (class "Default")
      (node (ref "XFMR2") (pin "10") (pinfunction "10_10") (pintype "passive"))
    )
    (net (code "88") (name "unconnected-(XFMR2-Pad11)") (class "Default")
      (node (ref "XFMR2") (pin "11") (pinfunction "11_11") (pintype "passive"))
    )
    (net (code "89") (name "unconnected-(XFMR2-Pad12)") (class "Default")
      (node (ref "XFMR2") (pin "12") (pinfunction "12_12") (pintype "passive"))
    )
  )
)
